# RGB_attiny2313.net
KiCad netlist of a schematic drawn in Altium Designer
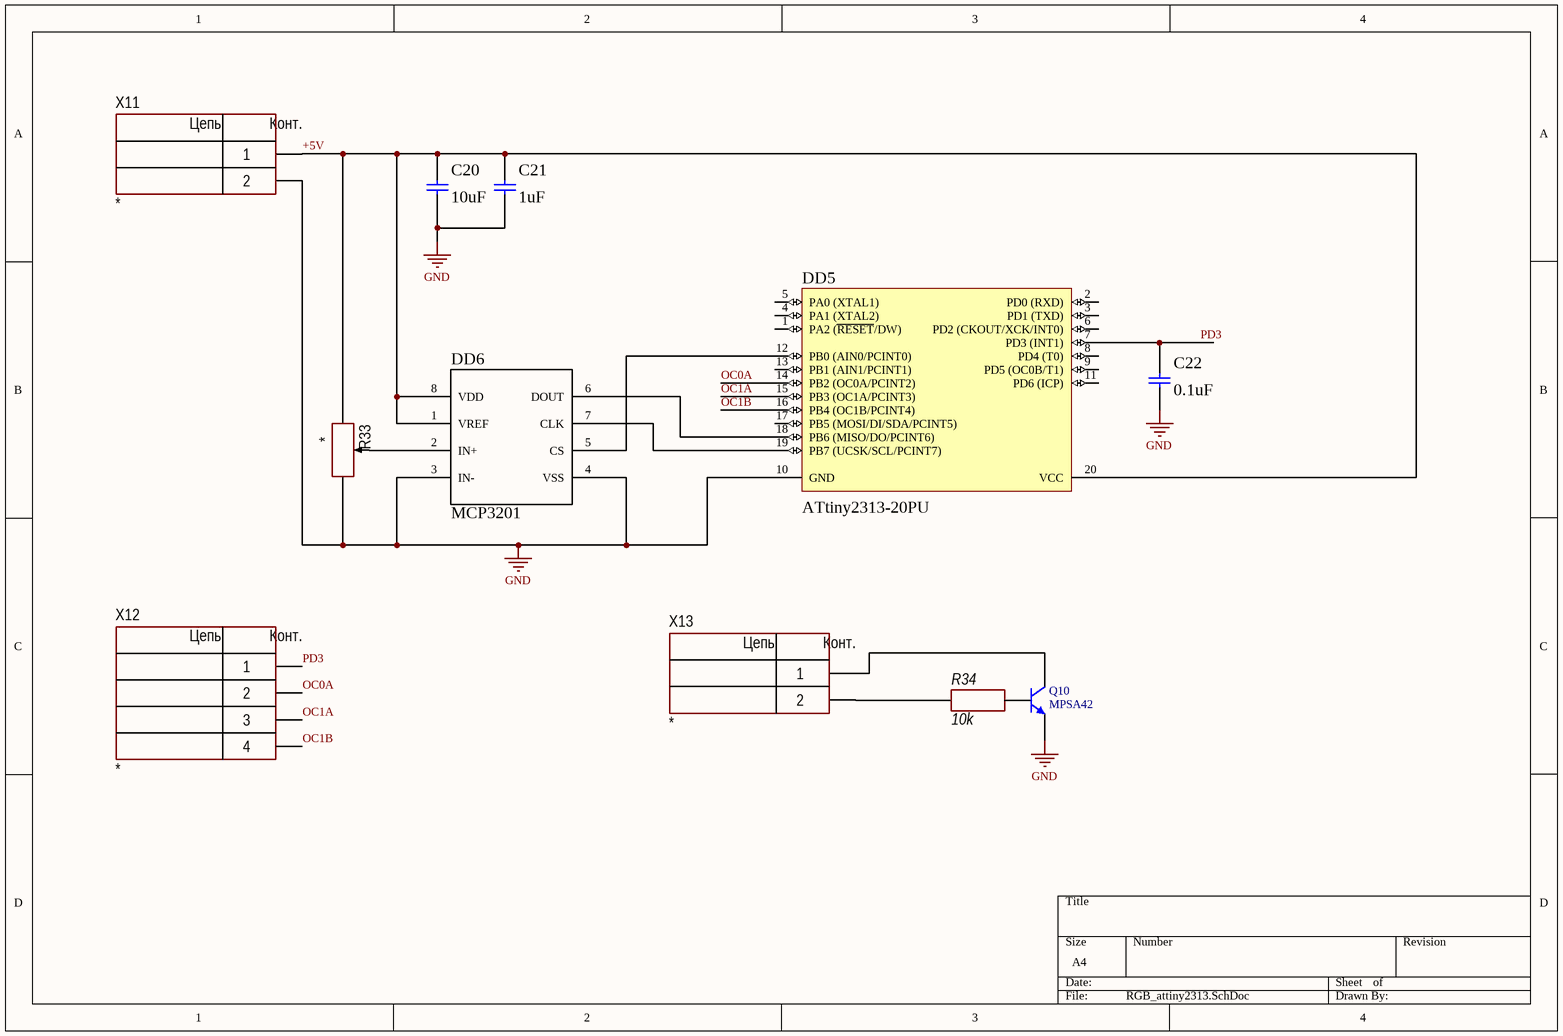
[diagram p0: RGB_attiny2313.SchDoc]

(export (version "E")
  (design (tool "Eeschema 10.0.6"))
  (components
    (comp (ref "C20")
      (value "10uF")
      (footprint "C1206")
      (description "Capacitor (Semiconductor SIM Model)")
      (fields (field (name "Comment") "Cap Semi") (field (name "PUBLISHER") "Altium Limited"))
      (libsource (lib "Miscellaneous Devices") (part "Cap Semi"))
    )
    (comp (ref "C21")
      (value "1uF")
      (footprint "C1206")
      (description "Capacitor (Semiconductor SIM Model)")
      (fields (field (name "Comment") "Cap Semi") (field (name "PUBLISHER") "Altium Limited"))
      (libsource (lib "Miscellaneous Devices") (part "Cap Semi"))
    )
    (comp (ref "C22")
      (value "0.1uF")
      (footprint "C1206")
      (description "Capacitor (Semiconductor SIM Model)")
      (fields (field (name "Comment") "Cap Semi") (field (name "PUBLISHER") "Altium Limited"))
      (libsource (lib "Miscellaneous Devices") (part "Cap Semi"))
    )
    (comp (ref "DD5")
      (value "ATtiny2313-20PU")
      (footprint "20P3")
      (fields (field (name "PUBLISHER") "Altium Limited"))
      (libsource (lib "Atmel Microcontroller 8-Bit tinyAVR") (part "ATtiny2313-20PU"))
    )
    (comp (ref "DD6")
      (value "MCP3201")
      (footprint "MAX1771_DIP8 - duplicate")
      (libsource (lib "MCP3201") (part "MCP3201"))
    )
    (comp (ref "Q10")
      (value "MPSA42")
      (footprint "TO-92A")
      (description "NPN General Purpose Amplifier")
      (fields (field (name "PUBLISHER") "Altium Limited"))
      (libsource (lib "Miscellaneous Devices") (part "2N3904"))
    )
    (comp (ref "R33") (value "*") (footprint "RES: 3362P") (libsource (lib "Discrete") (part "ADJ resistor")))
    (comp (ref "R34")
      (value "10k")
      (footprint "MLT")
      (description "MLT")
      (libsource (lib "Resistor_MLT") (part "Resistor"))
    )
    (comp (ref "X11")
      (value "*")
      (footprint "CON: WJ06-02P")
      (libsource (lib "Connectors") (part "2-Connector"))
    )
    (comp (ref "X12")
      (value "*")
      (footprint "custom:CON: PBS-4")
      (libsource (lib "Connectors") (part "4-Connector"))
    )
    (comp (ref "X13")
      (value "*")
      (footprint "CON: PBS-2")
      (libsource (lib "Connectors") (part "2-Connector"))
    )
  )
  (nets
    (net (code "1") (name "/+5V") (class "Default")
      (node (ref "C20") (pin "2") (pinfunction "2_2") (pintype "passive"))
      (node (ref "C21") (pin "2") (pinfunction "2_2") (pintype "passive"))
      (node (ref "DD5") (pin "20") (pinfunction "VCC_20") (pintype "power_in"))
      (node (ref "DD6") (pin "1") (pinfunction "VREF_1") (pintype "passive"))
      (node (ref "DD6") (pin "8") (pinfunction "VDD_8") (pintype "passive"))
      (node (ref "R33") (pin "1") (pinfunction "1_1") (pintype "passive"))
      (node (ref "X11") (pin "1") (pinfunction "1_1") (pintype "passive"))
    )
    (net (code "2") (name "/OC0A") (class "Default")
      (node (ref "DD5") (pin "14") (pinfunction "PB2_(OC0A/PCINT2)_14") (pintype "bidirectional"))
      (node (ref "X12") (pin "2") (pinfunction "2_2") (pintype "passive"))
    )
    (net (code "3") (name "/OC1A") (class "Default")
      (node (ref "DD5") (pin "15") (pinfunction "PB3_(OC1A/PCINT3)_15") (pintype "bidirectional"))
      (node (ref "X12") (pin "3") (pinfunction "3_3") (pintype "power_in"))
    )
    (net (code "4") (name "/OC1B") (class "Default")
      (node (ref "DD5") (pin "16") (pinfunction "PB4_(OC1B/PCINT4)_16") (pintype "bidirectional"))
      (node (ref "X12") (pin "4") (pinfunction "4_4") (pintype "power_in"))
    )
    (net (code "5") (name "/PD3") (class "Default")
      (node (ref "C22") (pin "2") (pinfunction "2_2") (pintype "passive"))
      (node (ref "DD5") (pin "7") (pinfunction "PD3_(INT1)_7") (pintype "bidirectional"))
      (node (ref "X12") (pin "1") (pinfunction "1_1") (pintype "passive"))
    )
    (net (code "6") (name "GND") (class "Default")
      (node (ref "C20") (pin "1") (pinfunction "1_1") (pintype "passive"))
      (node (ref "C21") (pin "1") (pinfunction "1_1") (pintype "passive"))
      (node (ref "C22") (pin "1") (pinfunction "1_1") (pintype "passive"))
      (node (ref "DD5") (pin "10") (pinfunction "GND_10") (pintype "power_in"))
      (node (ref "DD6") (pin "3") (pinfunction "IN-_3") (pintype "passive"))
      (node (ref "DD6") (pin "4") (pinfunction "VSS_4") (pintype "passive"))
      (node (ref "Q10") (pin "1") (pinfunction "E_1") (pintype "passive"))
      (node (ref "R33") (pin "3") (pinfunction "3_3") (pintype "passive"))
      (node (ref "X11") (pin "2") (pinfunction "2_2") (pintype "passive"))
    )
    (net (code "7") (name "Net-(DD5-PB0_(AIN0{slash}PCINT0))") (class "Default")
      (node (ref "DD5") (pin "12") (pinfunction "PB0_(AIN0/PCINT0)_12") (pintype "bidirectional"))
      (node (ref "DD6") (pin "5") (pinfunction "CS_5") (pintype "passive"))
    )
    (net (code "8") (name "Net-(DD5-PB6_(MISO{slash}DO{slash}PCINT6))") (class "Default")
      (node (ref "DD5") (pin "18") (pinfunction "PB6_(MISO/DO/PCINT6)_18") (pintype "bidirectional"))
      (node (ref "DD6") (pin "6") (pinfunction "DOUT_6") (pintype "passive"))
    )
    (net (code "9") (name "Net-(DD5-PB7_(UCSK{slash}SCL{slash}PCINT7))") (class "Default")
      (node (ref "DD5") (pin "19") (pinfunction "PB7_(UCSK/SCL/PCINT7)_19") (pintype "bidirectional"))
      (node (ref "DD6") (pin "7") (pinfunction "CLK_7") (pintype "passive"))
    )
    (net (code "10") (name "Net-(DD6-IN+)") (class "Default")
      (node (ref "DD6") (pin "2") (pinfunction "IN+_2") (pintype "passive"))
      (node (ref "R33") (pin "2") (pinfunction "2_2") (pintype "passive"))
    )
    (net (code "11") (name "Net-(Q10-B)") (class "Default")
      (node (ref "Q10") (pin "2") (pinfunction "B_2") (pintype "passive"))
      (node (ref "R34") (pin "1") (pintype "passive"))
    )
    (net (code "12") (name "Net-(Q10-C)") (class "Default")
      (node (ref "Q10") (pin "3") (pinfunction "C_3") (pintype "passive"))
      (node (ref "X13") (pin "1") (pinfunction "1_1") (pintype "passive"))
    )
    (net (code "13") (name "Net-(R34-Pad2)") (class "Default")
      (node (ref "R34") (pin "2") (pintype "passive"))
      (node (ref "X13") (pin "2") (pinfunction "2_2") (pintype "passive"))
    )
    (net (code "14") (name "unconnected-(DD5-PA0_(XTAL1)-Pad5)") (class "Default")
      (node (ref "DD5") (pin "5") (pinfunction "PA0_(XTAL1)_5") (pintype "bidirectional"))
    )
    (net (code "15") (name "unconnected-(DD5-PA1_(XTAL2)-Pad4)") (class "Default")
      (node (ref "DD5") (pin "4") (pinfunction "PA1_(XTAL2)_4") (pintype "bidirectional"))
    )
    (net (code "16") (name "unconnected-(DD5-PA2_(~{RESET}{slash}DW)-Pad1)") (class "Default")
      (node (ref "DD5") (pin "1") (pinfunction "PA2_(~{RESET}/DW)_1") (pintype "bidirectional"))
    )
    (net (code "17") (name "unconnected-(DD5-PB1_(AIN1{slash}PCINT1)-Pad13)") (class "Default")
      (node (ref "DD5") (pin "13") (pinfunction "PB1_(AIN1/PCINT1)_13") (pintype "bidirectional"))
    )
    (net (code "18") (name "unconnected-(DD5-PB5_(MOSI{slash}DI{slash}SDA{slash}PCINT5)-Pad17)") (class "Default")
      (node (ref "DD5") (pin "17") (pinfunction "PB5_(MOSI/DI/SDA/PCINT5)_17") (pintype "bidirectional"))
    )
    (net (code "19") (name "unconnected-(DD5-PD0_(RXD)-Pad2)") (class "Default")
      (node (ref "DD5") (pin "2") (pinfunction "PD0_(RXD)_2") (pintype "bidirectional"))
    )
    (net (code "20") (name "unconnected-(DD5-PD1_(TXD)-Pad3)") (class "Default")
      (node (ref "DD5") (pin "3") (pinfunction "PD1_(TXD)_3") (pintype "bidirectional"))
    )
    (net (code "21") (name "unconnected-(DD5-PD2_(CKOUT{slash}XCK{slash}INT0)-Pad6)") (class "Default")
      (node (ref "DD5") (pin "6") (pinfunction "PD2_(CKOUT/XCK/INT0)_6") (pintype "bidirectional"))
    )
    (net (code "22") (name "unconnected-(DD5-PD4_(T0)-Pad8)") (class "Default")
      (node (ref "DD5") (pin "8") (pinfunction "PD4_(T0)_8") (pintype "bidirectional"))
    )
    (net (code "23") (name "unconnected-(DD5-PD5_(OC0B{slash}T1)-Pad9)") (class "Default")
      (node (ref "DD5") (pin "9") (pinfunction "PD5_(OC0B/T1)_9") (pintype "bidirectional"))
    )
    (net (code "24") (name "unconnected-(DD5-PD6_(ICP)-Pad11)") (class "Default")
      (node (ref "DD5") (pin "11") (pinfunction "PD6_(ICP)_11") (pintype "bidirectional"))
    )
  )
)
